# tracksoar_chip_breakout_shield.net
KiCad netlist of a schematic drawn in EAGLE
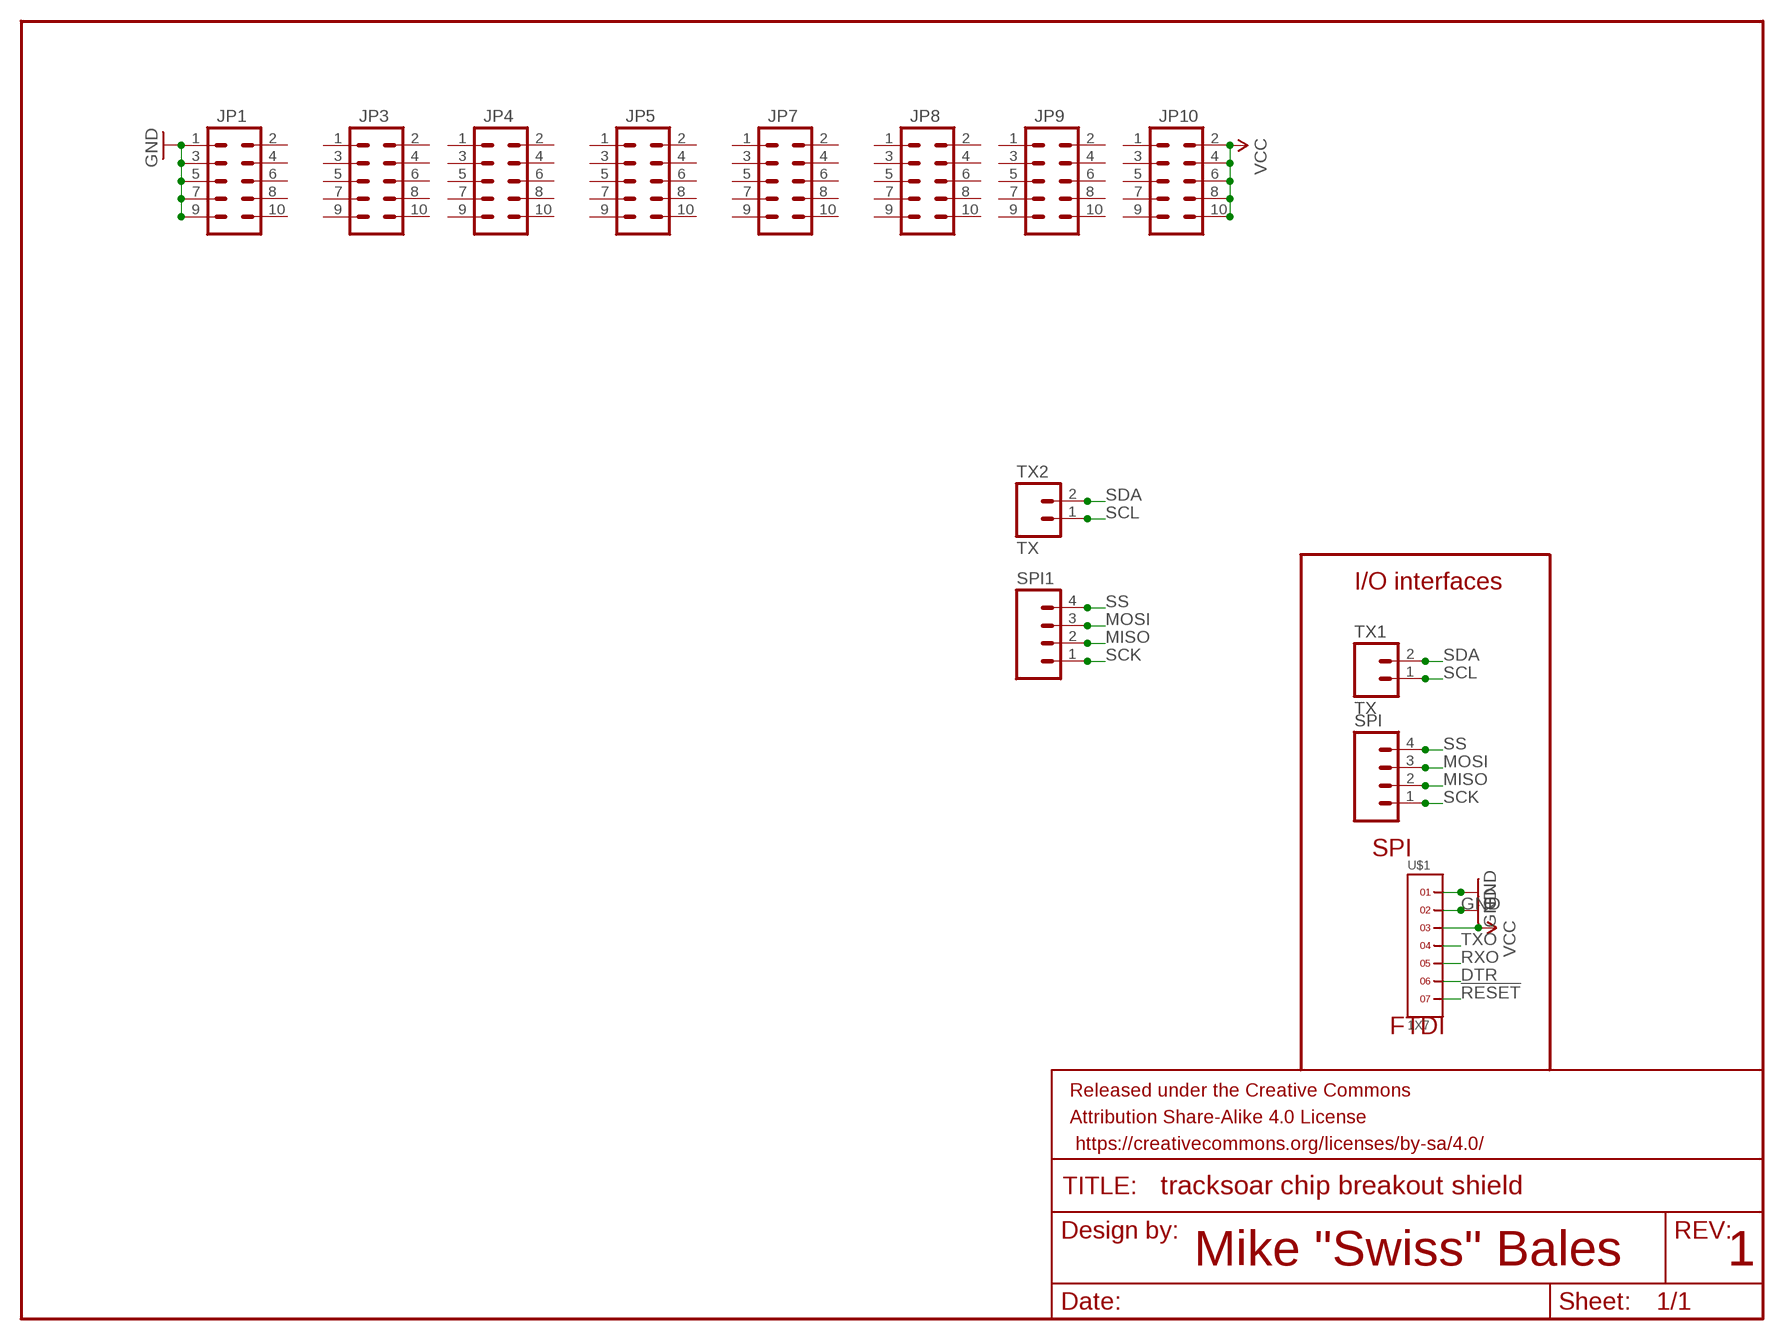
[diagram p0: schematic, sheet 1]

(export (version "E")
  (design (tool "Eeschema 10.0.6"))
  (components
    (comp (ref "FRAME1")
      (value "FRAME-LETTER")
      (footprint "eagle-import:CREATIVE_COMMONS")
      (libsource (lib "eagle-import") (part "FRAME-LETTER"))
    )
    (comp (ref "JP1")
      (value "M05X2NO_SILK")
      (footprint "eagle-import:2X5_NOSILK")
      (libsource (lib "eagle-import") (part "M05X2NO_SILK"))
    )
    (comp (ref "JP3")
      (value "M05X2NO_SILK")
      (footprint "eagle-import:2X5_NOSILK")
      (libsource (lib "eagle-import") (part "M05X2NO_SILK"))
    )
    (comp (ref "JP4")
      (value "M05X2NO_SILK")
      (footprint "eagle-import:2X5_NOSILK")
      (libsource (lib "eagle-import") (part "M05X2NO_SILK"))
    )
    (comp (ref "JP5")
      (value "M05X2NO_SILK")
      (footprint "eagle-import:2X5_NOSILK")
      (libsource (lib "eagle-import") (part "M05X2NO_SILK"))
    )
    (comp (ref "JP7")
      (value "M05X2NO_SILK")
      (footprint "eagle-import:2X5_NOSILK")
      (libsource (lib "eagle-import") (part "M05X2NO_SILK"))
    )
    (comp (ref "JP8")
      (value "M05X2NO_SILK")
      (footprint "eagle-import:2X5_NOSILK")
      (libsource (lib "eagle-import") (part "M05X2NO_SILK"))
    )
    (comp (ref "JP9")
      (value "M05X2NO_SILK")
      (footprint "eagle-import:2X5_NOSILK")
      (libsource (lib "eagle-import") (part "M05X2NO_SILK"))
    )
    (comp (ref "JP10")
      (value "M05X2NO_SILK")
      (footprint "eagle-import:2X5_NOSILK")
      (libsource (lib "eagle-import") (part "M05X2NO_SILK"))
    )
    (comp (ref "SPI")
      (value "M04JST-PTH-VERT")
      (footprint "eagle-import:JST-4-PTH-VERT")
      (libsource (lib "eagle-import") (part "M04JST-PTH-VERT"))
    )
    (comp (ref "SPI1")
      (value "M04JST-PTH-VERT")
      (footprint "eagle-import:JST-4-PTH-VERT")
      (libsource (lib "eagle-import") (part "M04JST-PTH-VERT"))
    )
    (comp (ref "TX1")
      (value "TX")
      (footprint "eagle-import:JST-2-PTH-VERT")
      (libsource (lib "eagle-import") (part "M02JST-PTH-VERT"))
    )
    (comp (ref "TX2")
      (value "TX")
      (footprint "eagle-import:JST-2-PTH-VERT")
      (libsource (lib "eagle-import") (part "M02JST-PTH-VERT"))
    )
    (comp (ref "U$1")
      (value "1X7")
      (footprint "eagle-import:1X7")
      (libsource (lib "eagle-import") (part "1X7"))
    )
  )
  (nets
    (net (code "1") (name "/DTR") (class "Default")
      (node (ref "U$1") (pin "6") (pinfunction "6_6") (pintype "bidirectional"))
    )
    (net (code "2") (name "/MISO") (class "Default")
      (node (ref "SPI") (pin "2") (pinfunction "2_2") (pintype "passive"))
      (node (ref "SPI1") (pin "2") (pinfunction "2_2") (pintype "passive"))
    )
    (net (code "3") (name "/MOSI") (class "Default")
      (node (ref "SPI") (pin "3") (pinfunction "3_3") (pintype "passive"))
      (node (ref "SPI1") (pin "3") (pinfunction "3_3") (pintype "passive"))
    )
    (net (code "4") (name "/RXO") (class "Default")
      (node (ref "U$1") (pin "5") (pinfunction "5_5") (pintype "bidirectional"))
    )
    (net (code "5") (name "/SCK") (class "Default")
      (node (ref "SPI") (pin "1") (pinfunction "1_1") (pintype "passive"))
      (node (ref "SPI1") (pin "1") (pinfunction "1_1") (pintype "passive"))
    )
    (net (code "6") (name "/SCL") (class "Default")
      (node (ref "TX1") (pin "1") (pinfunction "1_1") (pintype "passive"))
      (node (ref "TX2") (pin "1") (pinfunction "1_1") (pintype "passive"))
    )
    (net (code "7") (name "/SDA") (class "Default")
      (node (ref "TX1") (pin "2") (pinfunction "2_2") (pintype "passive"))
      (node (ref "TX2") (pin "2") (pinfunction "2_2") (pintype "passive"))
    )
    (net (code "8") (name "/SS") (class "Default")
      (node (ref "SPI") (pin "4") (pinfunction "4_4") (pintype "passive"))
      (node (ref "SPI1") (pin "4") (pinfunction "4_4") (pintype "passive"))
    )
    (net (code "9") (name "/TXO") (class "Default")
      (node (ref "U$1") (pin "4") (pinfunction "4_4") (pintype "bidirectional"))
    )
    (net (code "10") (name "/~{RESET}") (class "Default")
      (node (ref "U$1") (pin "7") (pinfunction "7_7") (pintype "bidirectional"))
    )
    (net (code "11") (name "GND") (class "Default")
      (node (ref "JP1") (pin "1") (pinfunction "1_1") (pintype "passive"))
      (node (ref "JP1") (pin "3") (pinfunction "3_3") (pintype "passive"))
      (node (ref "JP1") (pin "5") (pinfunction "5_5") (pintype "passive"))
      (node (ref "JP1") (pin "7") (pinfunction "7_7") (pintype "passive"))
      (node (ref "JP1") (pin "9") (pinfunction "9_9") (pintype "passive"))
      (node (ref "U$1") (pin "1") (pinfunction "1_1") (pintype "bidirectional"))
      (node (ref "U$1") (pin "2") (pinfunction "2_2") (pintype "bidirectional"))
    )
    (net (code "12") (name "VCC") (class "Default")
      (node (ref "JP10") (pin "10") (pinfunction "10_10") (pintype "passive"))
      (node (ref "JP10") (pin "2") (pinfunction "2_2") (pintype "passive"))
      (node (ref "JP10") (pin "4") (pinfunction "4_4") (pintype "passive"))
      (node (ref "JP10") (pin "6") (pinfunction "6_6") (pintype "passive"))
      (node (ref "JP10") (pin "8") (pinfunction "8_8") (pintype "passive"))
      (node (ref "U$1") (pin "3") (pinfunction "3_3") (pintype "bidirectional"))
    )
    (net (code "13") (name "unconnected-(JP1-Pad2)") (class "Default")
      (node (ref "JP1") (pin "2") (pinfunction "2_2") (pintype "passive"))
    )
    (net (code "14") (name "unconnected-(JP1-Pad4)") (class "Default")
      (node (ref "JP1") (pin "4") (pinfunction "4_4") (pintype "passive"))
    )
    (net (code "15") (name "unconnected-(JP1-Pad6)") (class "Default")
      (node (ref "JP1") (pin "6") (pinfunction "6_6") (pintype "passive"))
    )
    (net (code "16") (name "unconnected-(JP1-Pad8)") (class "Default")
      (node (ref "JP1") (pin "8") (pinfunction "8_8") (pintype "passive"))
    )
    (net (code "17") (name "unconnected-(JP1-Pad10)") (class "Default")
      (node (ref "JP1") (pin "10") (pinfunction "10_10") (pintype "passive"))
    )
    (net (code "18") (name "unconnected-(JP3-Pad1)") (class "Default")
      (node (ref "JP3") (pin "1") (pinfunction "1_1") (pintype "passive"))
    )
    (net (code "19") (name "unconnected-(JP3-Pad2)") (class "Default")
      (node (ref "JP3") (pin "2") (pinfunction "2_2") (pintype "passive"))
    )
    (net (code "20") (name "unconnected-(JP3-Pad3)") (class "Default")
      (node (ref "JP3") (pin "3") (pinfunction "3_3") (pintype "passive"))
    )
    (net (code "21") (name "unconnected-(JP3-Pad4)") (class "Default")
      (node (ref "JP3") (pin "4") (pinfunction "4_4") (pintype "passive"))
    )
    (net (code "22") (name "unconnected-(JP3-Pad5)") (class "Default")
      (node (ref "JP3") (pin "5") (pinfunction "5_5") (pintype "passive"))
    )
    (net (code "23") (name "unconnected-(JP3-Pad6)") (class "Default")
      (node (ref "JP3") (pin "6") (pinfunction "6_6") (pintype "passive"))
    )
    (net (code "24") (name "unconnected-(JP3-Pad7)") (class "Default")
      (node (ref "JP3") (pin "7") (pinfunction "7_7") (pintype "passive"))
    )
    (net (code "25") (name "unconnected-(JP3-Pad8)") (class "Default")
      (node (ref "JP3") (pin "8") (pinfunction "8_8") (pintype "passive"))
    )
    (net (code "26") (name "unconnected-(JP3-Pad9)") (class "Default")
      (node (ref "JP3") (pin "9") (pinfunction "9_9") (pintype "passive"))
    )
    (net (code "27") (name "unconnected-(JP3-Pad10)") (class "Default")
      (node (ref "JP3") (pin "10") (pinfunction "10_10") (pintype "passive"))
    )
    (net (code "28") (name "unconnected-(JP4-Pad1)") (class "Default")
      (node (ref "JP4") (pin "1") (pinfunction "1_1") (pintype "passive"))
    )
    (net (code "29") (name "unconnected-(JP4-Pad2)") (class "Default")
      (node (ref "JP4") (pin "2") (pinfunction "2_2") (pintype "passive"))
    )
    (net (code "30") (name "unconnected-(JP4-Pad3)") (class "Default")
      (node (ref "JP4") (pin "3") (pinfunction "3_3") (pintype "passive"))
    )
    (net (code "31") (name "unconnected-(JP4-Pad4)") (class "Default")
      (node (ref "JP4") (pin "4") (pinfunction "4_4") (pintype "passive"))
    )
    (net (code "32") (name "unconnected-(JP4-Pad5)") (class "Default")
      (node (ref "JP4") (pin "5") (pinfunction "5_5") (pintype "passive"))
    )
    (net (code "33") (name "unconnected-(JP4-Pad6)") (class "Default")
      (node (ref "JP4") (pin "6") (pinfunction "6_6") (pintype "passive"))
    )
    (net (code "34") (name "unconnected-(JP4-Pad7)") (class "Default")
      (node (ref "JP4") (pin "7") (pinfunction "7_7") (pintype "passive"))
    )
    (net (code "35") (name "unconnected-(JP4-Pad8)") (class "Default")
      (node (ref "JP4") (pin "8") (pinfunction "8_8") (pintype "passive"))
    )
    (net (code "36") (name "unconnected-(JP4-Pad9)") (class "Default")
      (node (ref "JP4") (pin "9") (pinfunction "9_9") (pintype "passive"))
    )
    (net (code "37") (name "unconnected-(JP4-Pad10)") (class "Default")
      (node (ref "JP4") (pin "10") (pinfunction "10_10") (pintype "passive"))
    )
    (net (code "38") (name "unconnected-(JP5-Pad1)") (class "Default")
      (node (ref "JP5") (pin "1") (pinfunction "1_1") (pintype "passive"))
    )
    (net (code "39") (name "unconnected-(JP5-Pad2)") (class "Default")
      (node (ref "JP5") (pin "2") (pinfunction "2_2") (pintype "passive"))
    )
    (net (code "40") (name "unconnected-(JP5-Pad3)") (class "Default")
      (node (ref "JP5") (pin "3") (pinfunction "3_3") (pintype "passive"))
    )
    (net (code "41") (name "unconnected-(JP5-Pad4)") (class "Default")
      (node (ref "JP5") (pin "4") (pinfunction "4_4") (pintype "passive"))
    )
    (net (code "42") (name "unconnected-(JP5-Pad5)") (class "Default")
      (node (ref "JP5") (pin "5") (pinfunction "5_5") (pintype "passive"))
    )
    (net (code "43") (name "unconnected-(JP5-Pad6)") (class "Default")
      (node (ref "JP5") (pin "6") (pinfunction "6_6") (pintype "passive"))
    )
    (net (code "44") (name "unconnected-(JP5-Pad7)") (class "Default")
      (node (ref "JP5") (pin "7") (pinfunction "7_7") (pintype "passive"))
    )
    (net (code "45") (name "unconnected-(JP5-Pad8)") (class "Default")
      (node (ref "JP5") (pin "8") (pinfunction "8_8") (pintype "passive"))
    )
    (net (code "46") (name "unconnected-(JP5-Pad9)") (class "Default")
      (node (ref "JP5") (pin "9") (pinfunction "9_9") (pintype "passive"))
    )
    (net (code "47") (name "unconnected-(JP5-Pad10)") (class "Default")
      (node (ref "JP5") (pin "10") (pinfunction "10_10") (pintype "passive"))
    )
    (net (code "48") (name "unconnected-(JP7-Pad1)") (class "Default")
      (node (ref "JP7") (pin "1") (pinfunction "1_1") (pintype "passive"))
    )
    (net (code "49") (name "unconnected-(JP7-Pad2)") (class "Default")
      (node (ref "JP7") (pin "2") (pinfunction "2_2") (pintype "passive"))
    )
    (net (code "50") (name "unconnected-(JP7-Pad3)") (class "Default")
      (node (ref "JP7") (pin "3") (pinfunction "3_3") (pintype "passive"))
    )
    (net (code "51") (name "unconnected-(JP7-Pad4)") (class "Default")
      (node (ref "JP7") (pin "4") (pinfunction "4_4") (pintype "passive"))
    )
    (net (code "52") (name "unconnected-(JP7-Pad5)") (class "Default")
      (node (ref "JP7") (pin "5") (pinfunction "5_5") (pintype "passive"))
    )
    (net (code "53") (name "unconnected-(JP7-Pad6)") (class "Default")
      (node (ref "JP7") (pin "6") (pinfunction "6_6") (pintype "passive"))
    )
    (net (code "54") (name "unconnected-(JP7-Pad7)") (class "Default")
      (node (ref "JP7") (pin "7") (pinfunction "7_7") (pintype "passive"))
    )
    (net (code "55") (name "unconnected-(JP7-Pad8)") (class "Default")
      (node (ref "JP7") (pin "8") (pinfunction "8_8") (pintype "passive"))
    )
    (net (code "56") (name "unconnected-(JP7-Pad9)") (class "Default")
      (node (ref "JP7") (pin "9") (pinfunction "9_9") (pintype "passive"))
    )
    (net (code "57") (name "unconnected-(JP7-Pad10)") (class "Default")
      (node (ref "JP7") (pin "10") (pinfunction "10_10") (pintype "passive"))
    )
    (net (code "58") (name "unconnected-(JP8-Pad1)") (class "Default")
      (node (ref "JP8") (pin "1") (pinfunction "1_1") (pintype "passive"))
    )
    (net (code "59") (name "unconnected-(JP8-Pad2)") (class "Default")
      (node (ref "JP8") (pin "2") (pinfunction "2_2") (pintype "passive"))
    )
    (net (code "60") (name "unconnected-(JP8-Pad3)") (class "Default")
      (node (ref "JP8") (pin "3") (pinfunction "3_3") (pintype "passive"))
    )
    (net (code "61") (name "unconnected-(JP8-Pad4)") (class "Default")
      (node (ref "JP8") (pin "4") (pinfunction "4_4") (pintype "passive"))
    )
    (net (code "62") (name "unconnected-(JP8-Pad5)") (class "Default")
      (node (ref "JP8") (pin "5") (pinfunction "5_5") (pintype "passive"))
    )
    (net (code "63") (name "unconnected-(JP8-Pad6)") (class "Default")
      (node (ref "JP8") (pin "6") (pinfunction "6_6") (pintype "passive"))
    )
    (net (code "64") (name "unconnected-(JP8-Pad7)") (class "Default")
      (node (ref "JP8") (pin "7") (pinfunction "7_7") (pintype "passive"))
    )
    (net (code "65") (name "unconnected-(JP8-Pad8)") (class "Default")
      (node (ref "JP8") (pin "8") (pinfunction "8_8") (pintype "passive"))
    )
    (net (code "66") (name "unconnected-(JP8-Pad9)") (class "Default")
      (node (ref "JP8") (pin "9") (pinfunction "9_9") (pintype "passive"))
    )
    (net (code "67") (name "unconnected-(JP8-Pad10)") (class "Default")
      (node (ref "JP8") (pin "10") (pinfunction "10_10") (pintype "passive"))
    )
    (net (code "68") (name "unconnected-(JP9-Pad1)") (class "Default")
      (node (ref "JP9") (pin "1") (pinfunction "1_1") (pintype "passive"))
    )
    (net (code "69") (name "unconnected-(JP9-Pad2)") (class "Default")
      (node (ref "JP9") (pin "2") (pinfunction "2_2") (pintype "passive"))
    )
    (net (code "70") (name "unconnected-(JP9-Pad3)") (class "Default")
      (node (ref "JP9") (pin "3") (pinfunction "3_3") (pintype "passive"))
    )
    (net (code "71") (name "unconnected-(JP9-Pad4)") (class "Default")
      (node (ref "JP9") (pin "4") (pinfunction "4_4") (pintype "passive"))
    )
    (net (code "72") (name "unconnected-(JP9-Pad5)") (class "Default")
      (node (ref "JP9") (pin "5") (pinfunction "5_5") (pintype "passive"))
    )
    (net (code "73") (name "unconnected-(JP9-Pad6)") (class "Default")
      (node (ref "JP9") (pin "6") (pinfunction "6_6") (pintype "passive"))
    )
    (net (code "74") (name "unconnected-(JP9-Pad7)") (class "Default")
      (node (ref "JP9") (pin "7") (pinfunction "7_7") (pintype "passive"))
    )
    (net (code "75") (name "unconnected-(JP9-Pad8)") (class "Default")
      (node (ref "JP9") (pin "8") (pinfunction "8_8") (pintype "passive"))
    )
    (net (code "76") (name "unconnected-(JP9-Pad9)") (class "Default")
      (node (ref "JP9") (pin "9") (pinfunction "9_9") (pintype "passive"))
    )
    (net (code "77") (name "unconnected-(JP9-Pad10)") (class "Default")
      (node (ref "JP9") (pin "10") (pinfunction "10_10") (pintype "passive"))
    )
    (net (code "78") (name "unconnected-(JP10-Pad1)") (class "Default")
      (node (ref "JP10") (pin "1") (pinfunction "1_1") (pintype "passive"))
    )
    (net (code "79") (name "unconnected-(JP10-Pad3)") (class "Default")
      (node (ref "JP10") (pin "3") (pinfunction "3_3") (pintype "passive"))
    )
    (net (code "80") (name "unconnected-(JP10-Pad5)") (class "Default")
      (node (ref "JP10") (pin "5") (pinfunction "5_5") (pintype "passive"))
    )
    (net (code "81") (name "unconnected-(JP10-Pad7)") (class "Default")
      (node (ref "JP10") (pin "7") (pinfunction "7_7") (pintype "passive"))
    )
    (net (code "82") (name "unconnected-(JP10-Pad9)") (class "Default")
      (node (ref "JP10") (pin "9") (pinfunction "9_9") (pintype "passive"))
    )
  )
)
